# Main.net
KiCad netlist of a schematic drawn in Altium Designer
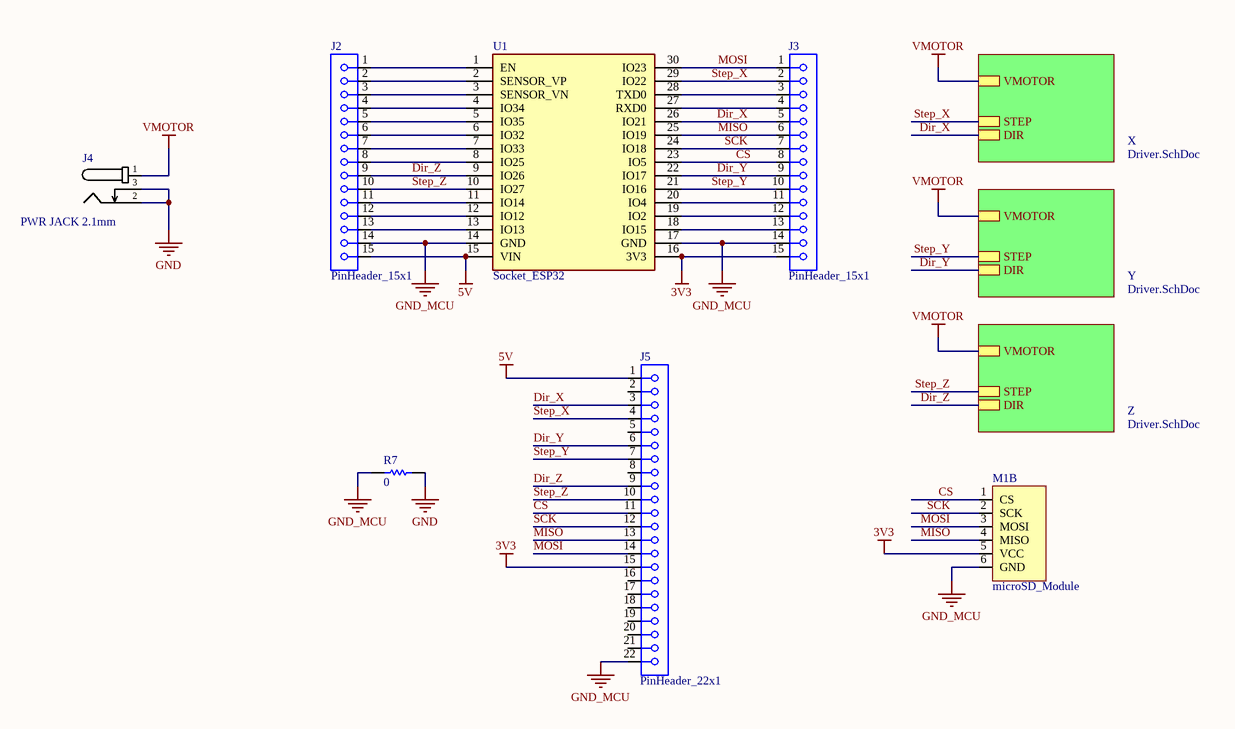
[diagram p0: Main.SchDoc]

(export (version "E")
  (design (tool "Eeschema 10.0.6"))
  (components
    (comp (ref "J2")
      (value "PinHeader_15x1")
      (footprint "PinHead_15x1")
      (libsource (lib "CNCLib") (part "PinHeader_15x1"))
    )
    (comp (ref "J3")
      (value "PinHeader_15x1")
      (footprint "PinHead_15x1")
      (libsource (lib "") (part "PinHeader_15x1_1"))
    )
    (comp (ref "J4")
      (value "PWR JACK 2.1mm")
      (footprint "CON_POWER_BARREL_2.1MM_3CONN")
      (description "CONN PWR JACK 2X5.5MM SOLDER")
      (fields (field (name "MANUFACTURER") "HCTL") (field (name "MANUFACTURER PART NUMBER") "HC-DC-005-2.0T"))
      (libsource (lib "CNCLib") (part "Con_Power_Jack_2.1mm_3pins"))
    )
    (comp (ref "J5")
      (value "PinHeader_22x1")
      (footprint "PinHead_22x1")
      (libsource (lib "CNCLib") (part "PinHeader_22x1"))
    )
    (comp (ref "M1")
      (value "microSD_Module")
      (footprint "MicroSD_Module_Vertical")
      (libsource (lib "CNCLib") (part "microSD_Module"))
    )
    (comp (ref "R7")
      (value "0")
      (footprint "RES_0805")
      (description "0 Ohms Jumper 0.25W, 1/4W Chip Resistor 0805 (2012 Metric) Automotive AEC-Q200 Thick Film")
      (fields
        (field (name "MANUFACTURER") "Vishay Dale")
        (field (name "MANUFACTURER PART NUMBER") "CRCW08050000Z0EA")
      )
      (libsource (lib "BOSTER2") (part "RES_0_0805"))
    )
    (comp (ref "U1")
      (value "Socket_ESP32")
      (footprint "Socket_ESP32")
      (libsource (lib "CNCLib") (part "Socket_ESP32"))
    )
  )
  (nets
    (net (code "1") (name "/CS") (class "Default")
      (node (ref "J3") (pin "8") (pintype "passive"))
      (node (ref "J5") (pin "11") (pintype "passive"))
      (node (ref "M1") (pin "1") (pinfunction "CS_1") (pintype "passive"))
      (node (ref "U1") (pin "23") (pinfunction "IO5_23") (pintype "passive"))
    )
    (net (code "2") (name "/Dir_X") (class "Default")
      (node (ref "J3") (pin "5") (pintype "passive"))
      (node (ref "J5") (pin "3") (pintype "passive"))
      (node (ref "U1") (pin "26") (pinfunction "IO21_26") (pintype "passive"))
    )
    (net (code "3") (name "/Dir_Y") (class "Default")
      (node (ref "J3") (pin "9") (pintype "passive"))
      (node (ref "J5") (pin "6") (pintype "passive"))
      (node (ref "U1") (pin "22") (pinfunction "IO17_22") (pintype "passive"))
    )
    (net (code "4") (name "/Dir_Z") (class "Default")
      (node (ref "J2") (pin "9") (pintype "passive"))
      (node (ref "J5") (pin "9") (pintype "passive"))
      (node (ref "U1") (pin "9") (pinfunction "IO26_9") (pintype "passive"))
    )
    (net (code "5") (name "/MISO") (class "Default")
      (node (ref "J3") (pin "6") (pintype "passive"))
      (node (ref "J5") (pin "13") (pintype "passive"))
      (node (ref "M1") (pin "4") (pinfunction "MISO_4") (pintype "passive"))
      (node (ref "U1") (pin "25") (pinfunction "IO19_25") (pintype "passive"))
    )
    (net (code "6") (name "/MOSI") (class "Default")
      (node (ref "J3") (pin "1") (pintype "passive"))
      (node (ref "J5") (pin "14") (pinfunction "14_14") (pintype "passive"))
      (node (ref "M1") (pin "3") (pinfunction "MOSI_3") (pintype "passive"))
      (node (ref "U1") (pin "30") (pinfunction "IO23_30") (pintype "passive"))
    )
    (net (code "7") (name "/SCK") (class "Default")
      (node (ref "J3") (pin "7") (pintype "passive"))
      (node (ref "J5") (pin "12") (pintype "passive"))
      (node (ref "M1") (pin "2") (pinfunction "SCK_2") (pintype "passive"))
      (node (ref "U1") (pin "24") (pinfunction "IO18_24") (pintype "passive"))
    )
    (net (code "8") (name "/Step_X") (class "Default")
      (node (ref "J3") (pin "2") (pintype "passive"))
      (node (ref "J5") (pin "4") (pintype "passive"))
      (node (ref "U1") (pin "29") (pinfunction "IO22_29") (pintype "passive"))
    )
    (net (code "9") (name "/Step_Y") (class "Default")
      (node (ref "J3") (pin "10") (pintype "passive"))
      (node (ref "J5") (pin "7") (pintype "passive"))
      (node (ref "U1") (pin "21") (pinfunction "IO16_21") (pintype "passive"))
    )
    (net (code "10") (name "/Step_Z") (class "Default")
      (node (ref "J2") (pin "10") (pintype "passive"))
      (node (ref "J5") (pin "10") (pintype "passive"))
      (node (ref "U1") (pin "10") (pinfunction "IO27_10") (pintype "passive"))
    )
    (net (code "11") (name "3V3") (class "Default")
      (node (ref "J3") (pin "15") (pinfunction "15_15") (pintype "passive"))
      (node (ref "J5") (pin "15") (pinfunction "15_15") (pintype "passive"))
      (node (ref "M1") (pin "5") (pinfunction "VCC_5") (pintype "passive"))
      (node (ref "U1") (pin "16") (pinfunction "3V3_16") (pintype "passive"))
    )
    (net (code "12") (name "5V") (class "Default")
      (node (ref "J2") (pin "15") (pinfunction "15_15") (pintype "passive"))
      (node (ref "J5") (pin "1") (pintype "passive"))
      (node (ref "U1") (pin "15") (pinfunction "VIN_15") (pintype "passive"))
    )
    (net (code "13") (name "GND") (class "Default")
      (node (ref "J4") (pin "2") (pinfunction "2_2") (pintype "passive"))
      (node (ref "J4") (pin "3") (pinfunction "3_3") (pintype "passive"))
      (node (ref "R7") (pin "2") (pinfunction "2_2") (pintype "passive"))
    )
    (net (code "14") (name "GND_MCU") (class "Default")
      (node (ref "J2") (pin "14") (pinfunction "14_14") (pintype "passive"))
      (node (ref "J3") (pin "14") (pinfunction "14_14") (pintype "passive"))
      (node (ref "J5") (pin "22") (pinfunction "22_22") (pintype "passive"))
      (node (ref "M1") (pin "6") (pinfunction "GND_6") (pintype "passive"))
      (node (ref "R7") (pin "1") (pinfunction "1_1") (pintype "passive"))
      (node (ref "U1") (pin "14") (pinfunction "GND_14") (pintype "passive"))
      (node (ref "U1") (pin "17") (pinfunction "GND_17") (pintype "passive"))
    )
    (net (code "15") (name "Net-(U1-EN)") (class "Default")
      (node (ref "J2") (pin "1") (pintype "passive"))
      (node (ref "U1") (pin "1") (pinfunction "EN_1") (pintype "passive"))
    )
    (net (code "16") (name "Net-(U1-IO2)") (class "Default")
      (node (ref "J3") (pin "12") (pintype "passive"))
      (node (ref "U1") (pin "19") (pinfunction "IO2_19") (pintype "passive"))
    )
    (net (code "17") (name "Net-(U1-IO4)") (class "Default")
      (node (ref "J3") (pin "11") (pintype "passive"))
      (node (ref "U1") (pin "20") (pinfunction "IO4_20") (pintype "passive"))
    )
    (net (code "18") (name "Net-(U1-IO12)") (class "Default")
      (node (ref "J2") (pin "12") (pintype "passive"))
      (node (ref "U1") (pin "12") (pinfunction "IO12_12") (pintype "passive"))
    )
    (net (code "19") (name "Net-(U1-IO13)") (class "Default")
      (node (ref "J2") (pin "13") (pintype "passive"))
      (node (ref "U1") (pin "13") (pinfunction "IO13_13") (pintype "passive"))
    )
    (net (code "20") (name "Net-(U1-IO14)") (class "Default")
      (node (ref "J2") (pin "11") (pintype "passive"))
      (node (ref "U1") (pin "11") (pinfunction "IO14_11") (pintype "passive"))
    )
    (net (code "21") (name "Net-(U1-IO15)") (class "Default")
      (node (ref "J3") (pin "13") (pintype "passive"))
      (node (ref "U1") (pin "18") (pinfunction "IO15_18") (pintype "passive"))
    )
    (net (code "22") (name "Net-(U1-IO25)") (class "Default")
      (node (ref "J2") (pin "8") (pintype "passive"))
      (node (ref "U1") (pin "8") (pinfunction "IO25_8") (pintype "passive"))
    )
    (net (code "23") (name "Net-(U1-IO32)") (class "Default")
      (node (ref "J2") (pin "6") (pintype "passive"))
      (node (ref "U1") (pin "6") (pinfunction "IO32_6") (pintype "passive"))
    )
    (net (code "24") (name "Net-(U1-IO33)") (class "Default")
      (node (ref "J2") (pin "7") (pintype "passive"))
      (node (ref "U1") (pin "7") (pinfunction "IO33_7") (pintype "passive"))
    )
    (net (code "25") (name "Net-(U1-IO34)") (class "Default")
      (node (ref "J2") (pin "4") (pintype "passive"))
      (node (ref "U1") (pin "4") (pinfunction "IO34_4") (pintype "passive"))
    )
    (net (code "26") (name "Net-(U1-IO35)") (class "Default")
      (node (ref "J2") (pin "5") (pintype "passive"))
      (node (ref "U1") (pin "5") (pinfunction "IO35_5") (pintype "passive"))
    )
    (net (code "27") (name "Net-(U1-RXD0)") (class "Default")
      (node (ref "J3") (pin "4") (pintype "passive"))
      (node (ref "U1") (pin "27") (pinfunction "RXD0_27") (pintype "passive"))
    )
    (net (code "28") (name "Net-(U1-SENSOR_VN)") (class "Default")
      (node (ref "J2") (pin "3") (pintype "passive"))
      (node (ref "U1") (pin "3") (pinfunction "SENSOR_VN_3") (pintype "passive"))
    )
    (net (code "29") (name "Net-(U1-SENSOR_VP)") (class "Default")
      (node (ref "J2") (pin "2") (pintype "passive"))
      (node (ref "U1") (pin "2") (pinfunction "SENSOR_VP_2") (pintype "passive"))
    )
    (net (code "30") (name "Net-(U1-TXD0)") (class "Default")
      (node (ref "J3") (pin "3") (pintype "passive"))
      (node (ref "U1") (pin "28") (pinfunction "TXD0_28") (pintype "passive"))
    )
    (net (code "31") (name "VMOTOR") (class "Default")
      (node (ref "J4") (pin "1") (pinfunction "1_1") (pintype "passive"))
    )
    (net (code "32") (name "unconnected-(J5-Pad2)") (class "Default")
      (node (ref "J5") (pin "2") (pintype "passive"))
    )
    (net (code "33") (name "unconnected-(J5-Pad5)") (class "Default")
      (node (ref "J5") (pin "5") (pintype "passive"))
    )
    (net (code "34") (name "unconnected-(J5-Pad8)") (class "Default")
      (node (ref "J5") (pin "8") (pintype "passive"))
    )
    (net (code "35") (name "unconnected-(J5-Pad16)") (class "Default")
      (node (ref "J5") (pin "16") (pinfunction "16_16") (pintype "passive"))
    )
    (net (code "36") (name "unconnected-(J5-Pad17)") (class "Default")
      (node (ref "J5") (pin "17") (pinfunction "17_17") (pintype "passive"))
    )
    (net (code "37") (name "unconnected-(J5-Pad18)") (class "Default")
      (node (ref "J5") (pin "18") (pinfunction "18_18") (pintype "passive"))
    )
    (net (code "38") (name "unconnected-(J5-Pad19)") (class "Default")
      (node (ref "J5") (pin "19") (pinfunction "19_19") (pintype "passive"))
    )
    (net (code "39") (name "unconnected-(J5-Pad20)") (class "Default")
      (node (ref "J5") (pin "20") (pinfunction "20_20") (pintype "passive"))
    )
    (net (code "40") (name "unconnected-(J5-Pad21)") (class "Default")
      (node (ref "J5") (pin "21") (pinfunction "21_21") (pintype "passive"))
    )
  )
)
